# boardv1.net
KiCad netlist of a schematic drawn in EAGLE
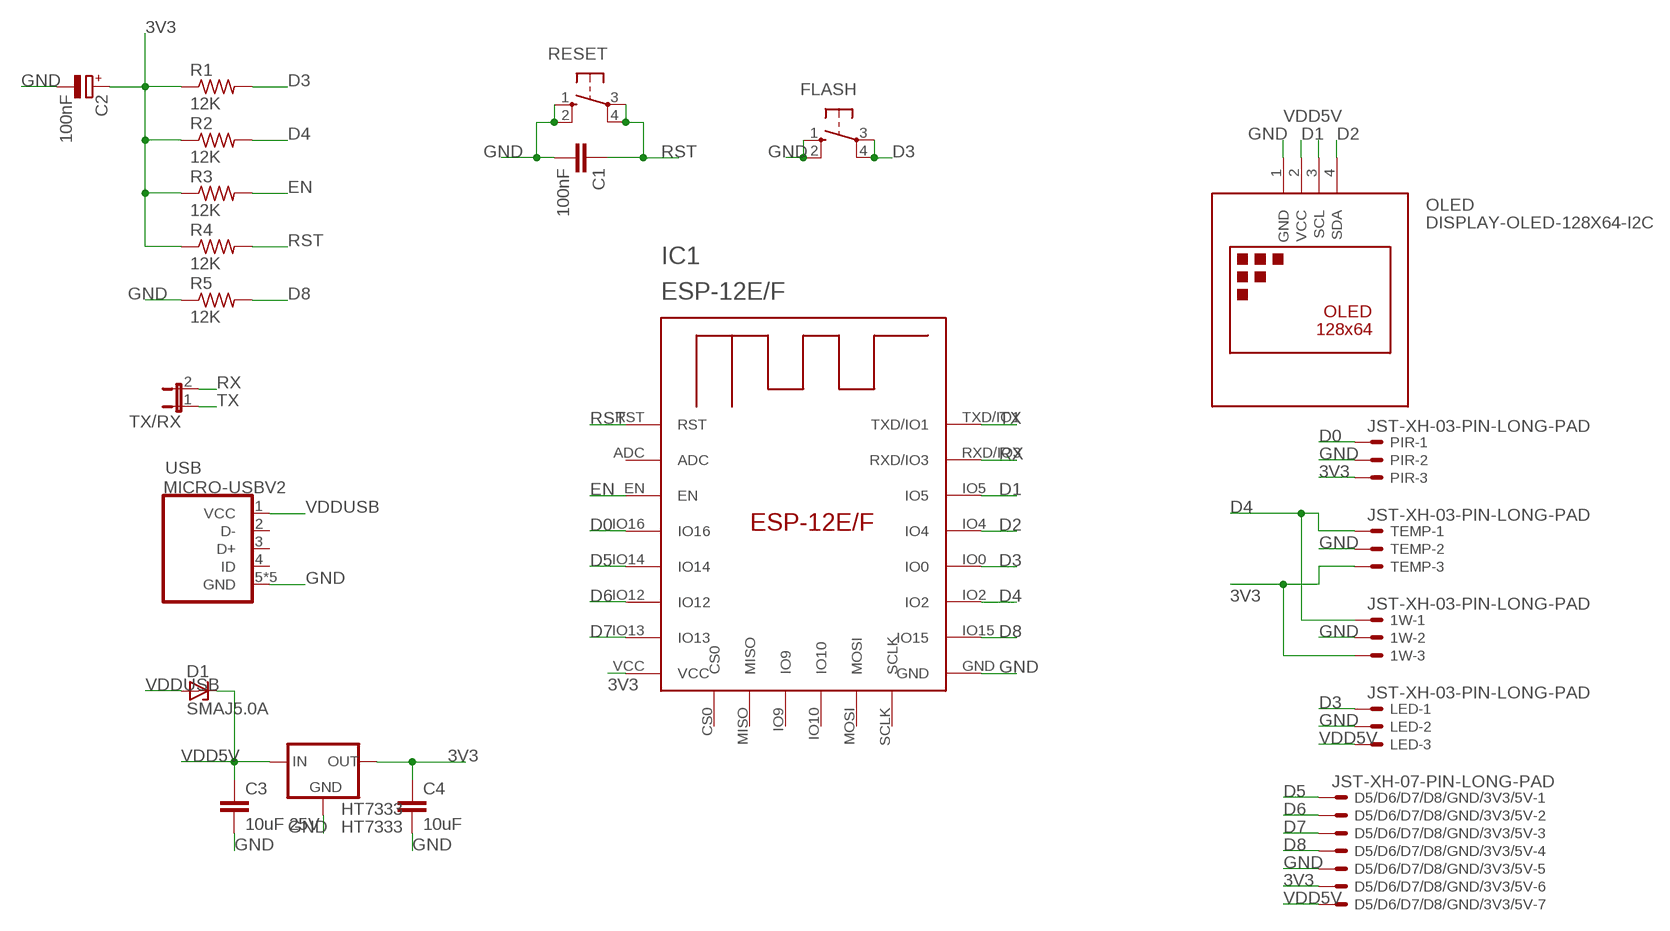
[diagram p0: schematic, sheet 1]

(export (version "E")
  (design (tool "Eeschema 10.0.6"))
  (components
    (comp (ref "1W")
      (value "JST-XH-03-PIN-LONG-PAD")
      (footprint "eagle-import:JST-XH-03-PACKAGE-LONG-PAD")
      (libsource (lib "eagle-import") (part "JST-XH-03-PIN-LONG-PAD"))
    )
    (comp (ref "C1")
      (value "100nF")
      (footprint "eagle-import:C0805")
      (libsource (lib "eagle-import") (part "C-EUC0805"))
    )
    (comp (ref "C2")
      (value "100nF")
      (footprint "eagle-import:R_2012-12R")
      (libsource (lib "eagle-import") (part "CPOL-EUR/2012-12R"))
    )
    (comp (ref "C3")
      (value "10uF 25V")
      (footprint "eagle-import:C0805")
      (libsource (lib "eagle-import") (part "C-EUC0805"))
    )
    (comp (ref "C4")
      (value "10uF")
      (footprint "eagle-import:C0805")
      (libsource (lib "eagle-import") (part "C-EUC0805"))
    )
    (comp (ref "D1")
      (value "SMAJ5.0A")
      (footprint "eagle-import:DO214AC")
      (fields (field (name "MF") "Littelfuse"))
      (libsource (lib "eagle-import") (part "SMAJA5.0"))
    )
    (comp (ref "D5/D6/D7/D8/GND/3V3/5V")
      (value "JST-XH-07-PIN-LONG-PAD")
      (footprint "eagle-import:JST-XH-07-PACKAGE-LONG-PAD")
      (libsource (lib "eagle-import") (part "JST-XH-07-PIN-LONG-PAD"))
    )
    (comp (ref "FLASH")
      (value "10-XX")
      (footprint "eagle-import:B3F-10XX")
      (fields (field (name "MPN") "B3F-1000"))
      (libsource (lib "eagle-import") (part "10-XX"))
    )
    (comp (ref "HT7333")
      (value "HT7333")
      (footprint "eagle-import:SOT-89")
      (libsource (lib "eagle-import") (part "HT7333"))
    )
    (comp (ref "IC1")
      (value "ESP-12E/F")
      (footprint "eagle-import:ESP-12E")
      (libsource (lib "eagle-import") (part "ESP-12E/F"))
    )
    (comp (ref "LED")
      (value "JST-XH-03-PIN-LONG-PAD")
      (footprint "eagle-import:JST-XH-03-PACKAGE-LONG-PAD")
      (libsource (lib "eagle-import") (part "JST-XH-03-PIN-LONG-PAD"))
    )
    (comp (ref "OLED")
      (value "DISPLAY-OLED-128X64-I2C")
      (footprint "eagle-import:DISPLAY-OLED-128X64-I2C")
      (libsource (lib "eagle-import") (part "DISPLAY-OLED-128X64-I2C"))
    )
    (comp (ref "PIR")
      (value "JST-XH-03-PIN-LONG-PAD")
      (footprint "eagle-import:JST-XH-03-PACKAGE-LONG-PAD")
      (libsource (lib "eagle-import") (part "JST-XH-03-PIN-LONG-PAD"))
    )
    (comp (ref "R1")
      (value "12K")
      (footprint "eagle-import:R1206")
      (fields (field (name "SPICEPREFIX") "R"))
      (libsource (lib "eagle-import") (part "R-US_R1206"))
    )
    (comp (ref "R2")
      (value "12K")
      (footprint "eagle-import:R1206")
      (libsource (lib "eagle-import") (part "R-US_R1206"))
    )
    (comp (ref "R3")
      (value "12K")
      (footprint "eagle-import:R1206")
      (libsource (lib "eagle-import") (part "R-US_R1206"))
    )
    (comp (ref "R4")
      (value "12K")
      (footprint "eagle-import:R1206")
      (libsource (lib "eagle-import") (part "R-US_R1206"))
    )
    (comp (ref "R5")
      (value "12K")
      (footprint "eagle-import:R1206")
      (libsource (lib "eagle-import") (part "R-US_R1206"))
    )
    (comp (ref "RESET")
      (value "10-XX")
      (footprint "eagle-import:B3F-10XX")
      (fields (field (name "MPN") "B3F-1000"))
      (libsource (lib "eagle-import") (part "10-XX"))
    )
    (comp (ref "TEMP")
      (value "JST-XH-03-PIN-LONG-PAD")
      (footprint "eagle-import:JST-XH-03-PACKAGE-LONG-PAD")
      (libsource (lib "eagle-import") (part "JST-XH-03-PIN-LONG-PAD"))
    )
    (comp (ref "TX/RX")
      (value "JP1E")
      (footprint "eagle-import:JP1")
      (libsource (lib "eagle-import") (part "JP1E"))
    )
    (comp (ref "USB")
      (value "MICRO-USBV2")
      (footprint "eagle-import:MICRO-USB-2")
      (libsource (lib "eagle-import") (part "MICRO-USBV2"))
    )
  )
  (nets
    (net (code "1") (name "/3V3") (class "Default")
      (node (ref "1W") (pin "3") (pinfunction "S_3") (pintype "passive"))
      (node (ref "C2") (pin "+") (pinfunction "+_+") (pintype "passive"))
      (node (ref "C4") (pin "1") (pinfunction "1_1") (pintype "passive"))
      (node (ref "D5/D6/D7/D8/GND/3V3/5V") (pin "6") (pinfunction "S_6") (pintype "passive"))
      (node (ref "HT7333") (pin "1") (pinfunction "OUT_1") (pintype "passive"))
      (node (ref "IC1") (pin "VCC") (pinfunction "VCC_VCC") (pintype "power_in"))
      (node (ref "PIR") (pin "3") (pinfunction "S_3") (pintype "passive"))
      (node (ref "R1") (pin "1") (pinfunction "1_1") (pintype "passive"))
      (node (ref "R2") (pin "1") (pinfunction "1_1") (pintype "passive"))
      (node (ref "R3") (pin "1") (pinfunction "1_1") (pintype "passive"))
      (node (ref "R4") (pin "1") (pinfunction "1_1") (pintype "passive"))
      (node (ref "TEMP") (pin "3") (pinfunction "S_3") (pintype "passive"))
    )
    (net (code "2") (name "/D0") (class "Default")
      (node (ref "IC1") (pin "IO16") (pinfunction "IO16_IO16") (pintype "bidirectional"))
      (node (ref "PIR") (pin "1") (pinfunction "S_1") (pintype "passive"))
    )
    (net (code "3") (name "/D1") (class "Default")
      (node (ref "IC1") (pin "IO5") (pinfunction "IO5_IO5") (pintype "bidirectional"))
      (node (ref "OLED") (pin "3") (pinfunction "SCL_3") (pintype "bidirectional"))
    )
    (net (code "4") (name "/D2") (class "Default")
      (node (ref "IC1") (pin "IO4") (pinfunction "IO4_IO4") (pintype "bidirectional"))
      (node (ref "OLED") (pin "4") (pinfunction "SDA_4") (pintype "bidirectional"))
    )
    (net (code "5") (name "/D3") (class "Default")
      (node (ref "FLASH") (pin "3") (pinfunction "P_3") (pintype "passive"))
      (node (ref "FLASH") (pin "4") (pinfunction "P1_4") (pintype "passive"))
      (node (ref "IC1") (pin "IO0") (pinfunction "IO0_IO0") (pintype "bidirectional"))
      (node (ref "LED") (pin "1") (pinfunction "S_1") (pintype "passive"))
      (node (ref "R1") (pin "2") (pinfunction "2_2") (pintype "passive"))
    )
    (net (code "6") (name "/D4") (class "Default")
      (node (ref "1W") (pin "1") (pinfunction "S_1") (pintype "passive"))
      (node (ref "IC1") (pin "IO2") (pinfunction "IO2_IO2") (pintype "bidirectional"))
      (node (ref "R2") (pin "2") (pinfunction "2_2") (pintype "passive"))
      (node (ref "TEMP") (pin "1") (pinfunction "S_1") (pintype "passive"))
    )
    (net (code "7") (name "/D5") (class "Default")
      (node (ref "D5/D6/D7/D8/GND/3V3/5V") (pin "1") (pinfunction "S_1") (pintype "passive"))
      (node (ref "IC1") (pin "IO14") (pinfunction "IO14_IO14") (pintype "bidirectional"))
    )
    (net (code "8") (name "/D6") (class "Default")
      (node (ref "D5/D6/D7/D8/GND/3V3/5V") (pin "2") (pinfunction "S_2") (pintype "passive"))
      (node (ref "IC1") (pin "IO12") (pinfunction "IO12_IO12") (pintype "bidirectional"))
    )
    (net (code "9") (name "/D7") (class "Default")
      (node (ref "D5/D6/D7/D8/GND/3V3/5V") (pin "3") (pinfunction "S_3") (pintype "passive"))
      (node (ref "IC1") (pin "IO13") (pinfunction "IO13_IO13") (pintype "bidirectional"))
    )
    (net (code "10") (name "/D8") (class "Default")
      (node (ref "D5/D6/D7/D8/GND/3V3/5V") (pin "4") (pinfunction "S_4") (pintype "passive"))
      (node (ref "IC1") (pin "IO15") (pinfunction "IO15_IO15") (pintype "bidirectional"))
      (node (ref "R5") (pin "2") (pinfunction "2_2") (pintype "passive"))
    )
    (net (code "11") (name "/EN") (class "Default")
      (node (ref "IC1") (pin "EN") (pinfunction "EN_EN") (pintype "bidirectional"))
      (node (ref "R3") (pin "2") (pinfunction "2_2") (pintype "passive"))
    )
    (net (code "12") (name "/GND") (class "Default")
      (node (ref "1W") (pin "2") (pinfunction "S_2") (pintype "passive"))
      (node (ref "C1") (pin "2") (pinfunction "2_2") (pintype "passive"))
      (node (ref "C2") (pin "-") (pinfunction "-_-") (pintype "passive"))
      (node (ref "C3") (pin "2") (pinfunction "2_2") (pintype "passive"))
      (node (ref "C4") (pin "2") (pinfunction "2_2") (pintype "passive"))
      (node (ref "D5/D6/D7/D8/GND/3V3/5V") (pin "5") (pinfunction "S_5") (pintype "passive"))
      (node (ref "FLASH") (pin "1") (pinfunction "S_1") (pintype "passive"))
      (node (ref "FLASH") (pin "2") (pinfunction "S1_2") (pintype "passive"))
      (node (ref "HT7333") (pin "2") (pinfunction "GND_2") (pintype "input"))
      (node (ref "IC1") (pin "GND") (pinfunction "GND_GND") (pintype "power_in"))
      (node (ref "LED") (pin "2") (pinfunction "S_2") (pintype "passive"))
      (node (ref "OLED") (pin "1") (pinfunction "GND_1") (pintype "power_in"))
      (node (ref "PIR") (pin "2") (pinfunction "S_2") (pintype "passive"))
      (node (ref "R5") (pin "1") (pinfunction "1_1") (pintype "passive"))
      (node (ref "RESET") (pin "1") (pinfunction "S_1") (pintype "passive"))
      (node (ref "RESET") (pin "2") (pinfunction "S1_2") (pintype "passive"))
      (node (ref "TEMP") (pin "2") (pinfunction "S_2") (pintype "passive"))
      (node (ref "USB") (pin "5") (pinfunction "GND_5") (pintype "power_in"))
      (node (ref "USB") (pin "P$1") (pinfunction "GND_P$1") (pintype "power_in"))
      (node (ref "USB") (pin "P$2") (pinfunction "GND_P$2") (pintype "power_in"))
      (node (ref "USB") (pin "P$3") (pinfunction "GND_P$3") (pintype "power_in"))
      (node (ref "USB") (pin "P$4") (pinfunction "GND_P$4") (pintype "power_in"))
    )
    (net (code "13") (name "/RST") (class "Default")
      (node (ref "C1") (pin "1") (pinfunction "1_1") (pintype "passive"))
      (node (ref "IC1") (pin "RST") (pinfunction "RST_RST") (pintype "input"))
      (node (ref "R4") (pin "2") (pinfunction "2_2") (pintype "passive"))
      (node (ref "RESET") (pin "3") (pinfunction "P_3") (pintype "passive"))
      (node (ref "RESET") (pin "4") (pinfunction "P1_4") (pintype "passive"))
    )
    (net (code "14") (name "/RX") (class "Default")
      (node (ref "IC1") (pin "RXD/IO3") (pinfunction "RXD/IO3_RXD/IO3") (pintype "bidirectional"))
      (node (ref "TX/RX") (pin "2") (pinfunction "2_2") (pintype "passive"))
    )
    (net (code "15") (name "/TX") (class "Default")
      (node (ref "IC1") (pin "TXD/IO1") (pinfunction "TXD/IO1_TXD/IO1") (pintype "bidirectional"))
      (node (ref "TX/RX") (pin "1") (pinfunction "1_1") (pintype "passive"))
    )
    (net (code "16") (name "/VDD5V") (class "Default")
      (node (ref "C3") (pin "1") (pinfunction "1_1") (pintype "passive"))
      (node (ref "D1") (pin "C") (pinfunction "C_C") (pintype "passive"))
      (node (ref "D5/D6/D7/D8/GND/3V3/5V") (pin "7") (pinfunction "S_7") (pintype "passive"))
      (node (ref "HT7333") (pin "3") (pinfunction "IN_3") (pintype "input"))
      (node (ref "HT7333") (pin "4") (pinfunction "IN_4") (pintype "input"))
      (node (ref "LED") (pin "3") (pinfunction "S_3") (pintype "passive"))
      (node (ref "OLED") (pin "2") (pinfunction "VCC_2") (pintype "power_in"))
    )
    (net (code "17") (name "/VDDUSB") (class "Default")
      (node (ref "D1") (pin "A") (pinfunction "A_A") (pintype "passive"))
      (node (ref "USB") (pin "1") (pinfunction "VCC_1") (pintype "power_in"))
    )
    (net (code "18") (name "unconnected-(IC1-PadADC)") (class "Default")
      (node (ref "IC1") (pin "ADC") (pinfunction "ADC_ADC") (pintype "bidirectional"))
    )
    (net (code "19") (name "unconnected-(IC1-PadCS0)") (class "Default")
      (node (ref "IC1") (pin "CS0") (pinfunction "CS0_CS0") (pintype "bidirectional"))
    )
    (net (code "20") (name "unconnected-(IC1-PadIO9)") (class "Default")
      (node (ref "IC1") (pin "IO9") (pinfunction "IO9_IO9") (pintype "bidirectional"))
    )
    (net (code "21") (name "unconnected-(IC1-PadIO10)") (class "Default")
      (node (ref "IC1") (pin "IO10") (pinfunction "IO10_IO10") (pintype "bidirectional"))
    )
    (net (code "22") (name "unconnected-(IC1-PadMISO)") (class "Default")
      (node (ref "IC1") (pin "MISO") (pinfunction "MISO_MISO") (pintype "bidirectional"))
    )
    (net (code "23") (name "unconnected-(IC1-PadMOSI)") (class "Default")
      (node (ref "IC1") (pin "MOSI") (pinfunction "MOSI_MOSI") (pintype "bidirectional"))
    )
    (net (code "24") (name "unconnected-(IC1-PadSCLK)") (class "Default")
      (node (ref "IC1") (pin "SCLK") (pinfunction "SCLK_SCLK") (pintype "bidirectional"))
    )
    (net (code "25") (name "unconnected-(USB-D+-Pad3)") (class "Default")
      (node (ref "USB") (pin "3") (pinfunction "D+_3") (pintype "bidirectional"))
    )
    (net (code "26") (name "unconnected-(USB-D--Pad2)") (class "Default")
      (node (ref "USB") (pin "2") (pinfunction "D-_2") (pintype "bidirectional"))
    )
    (net (code "27") (name "unconnected-(USB-ID-Pad4)") (class "Default")
      (node (ref "USB") (pin "4") (pinfunction "ID_4") (pintype "bidirectional"))
    )
  )
)
